# memory-32kx13.net
KiCad netlist of a schematic drawn in EAGLE
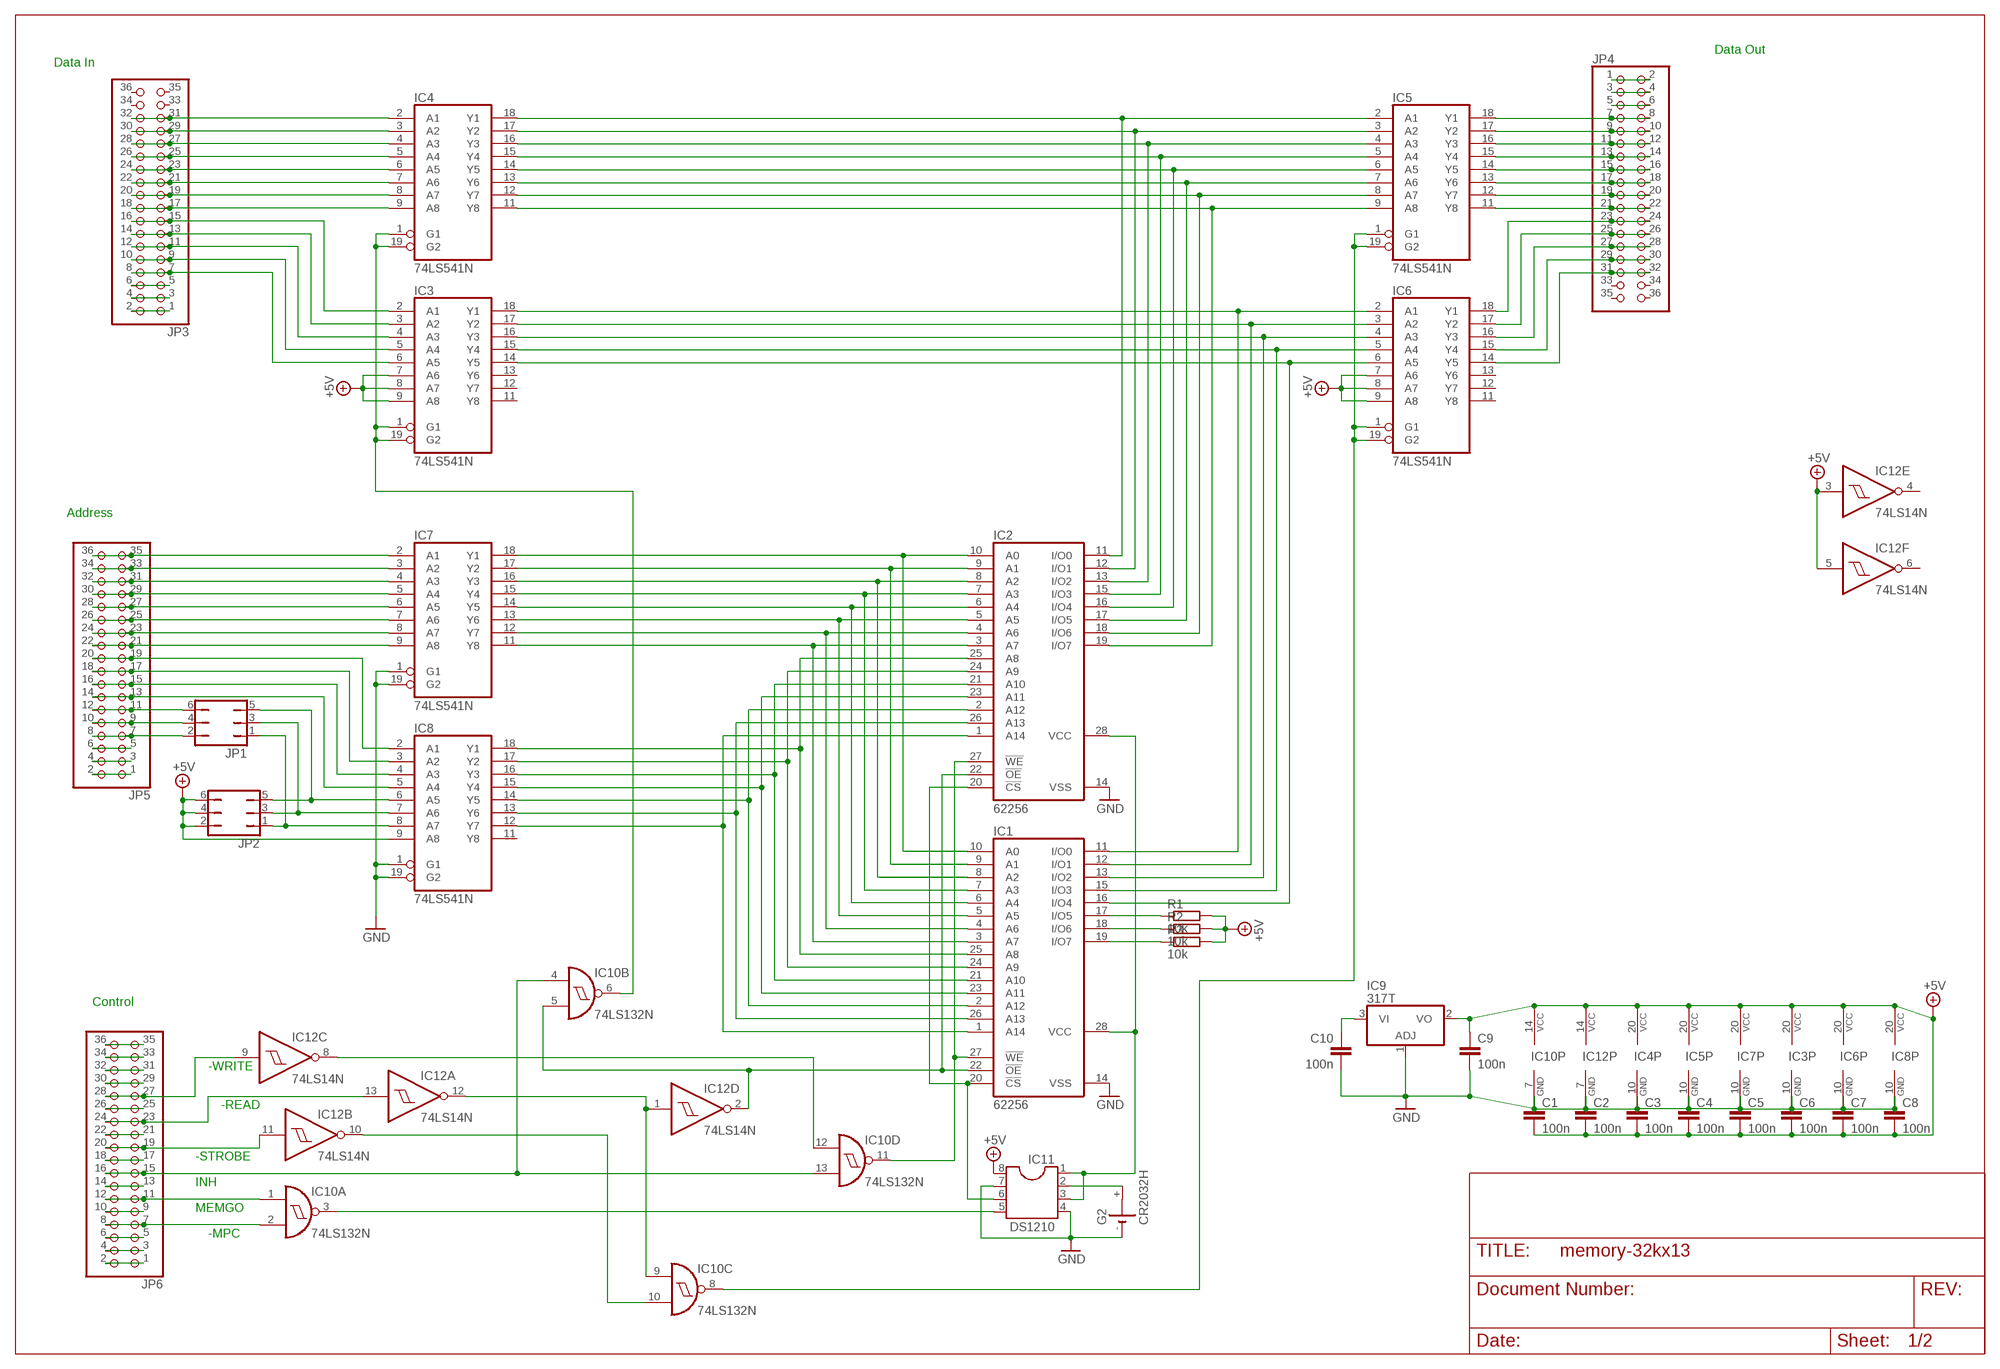
[diagram p0: schematic, sheet 1]
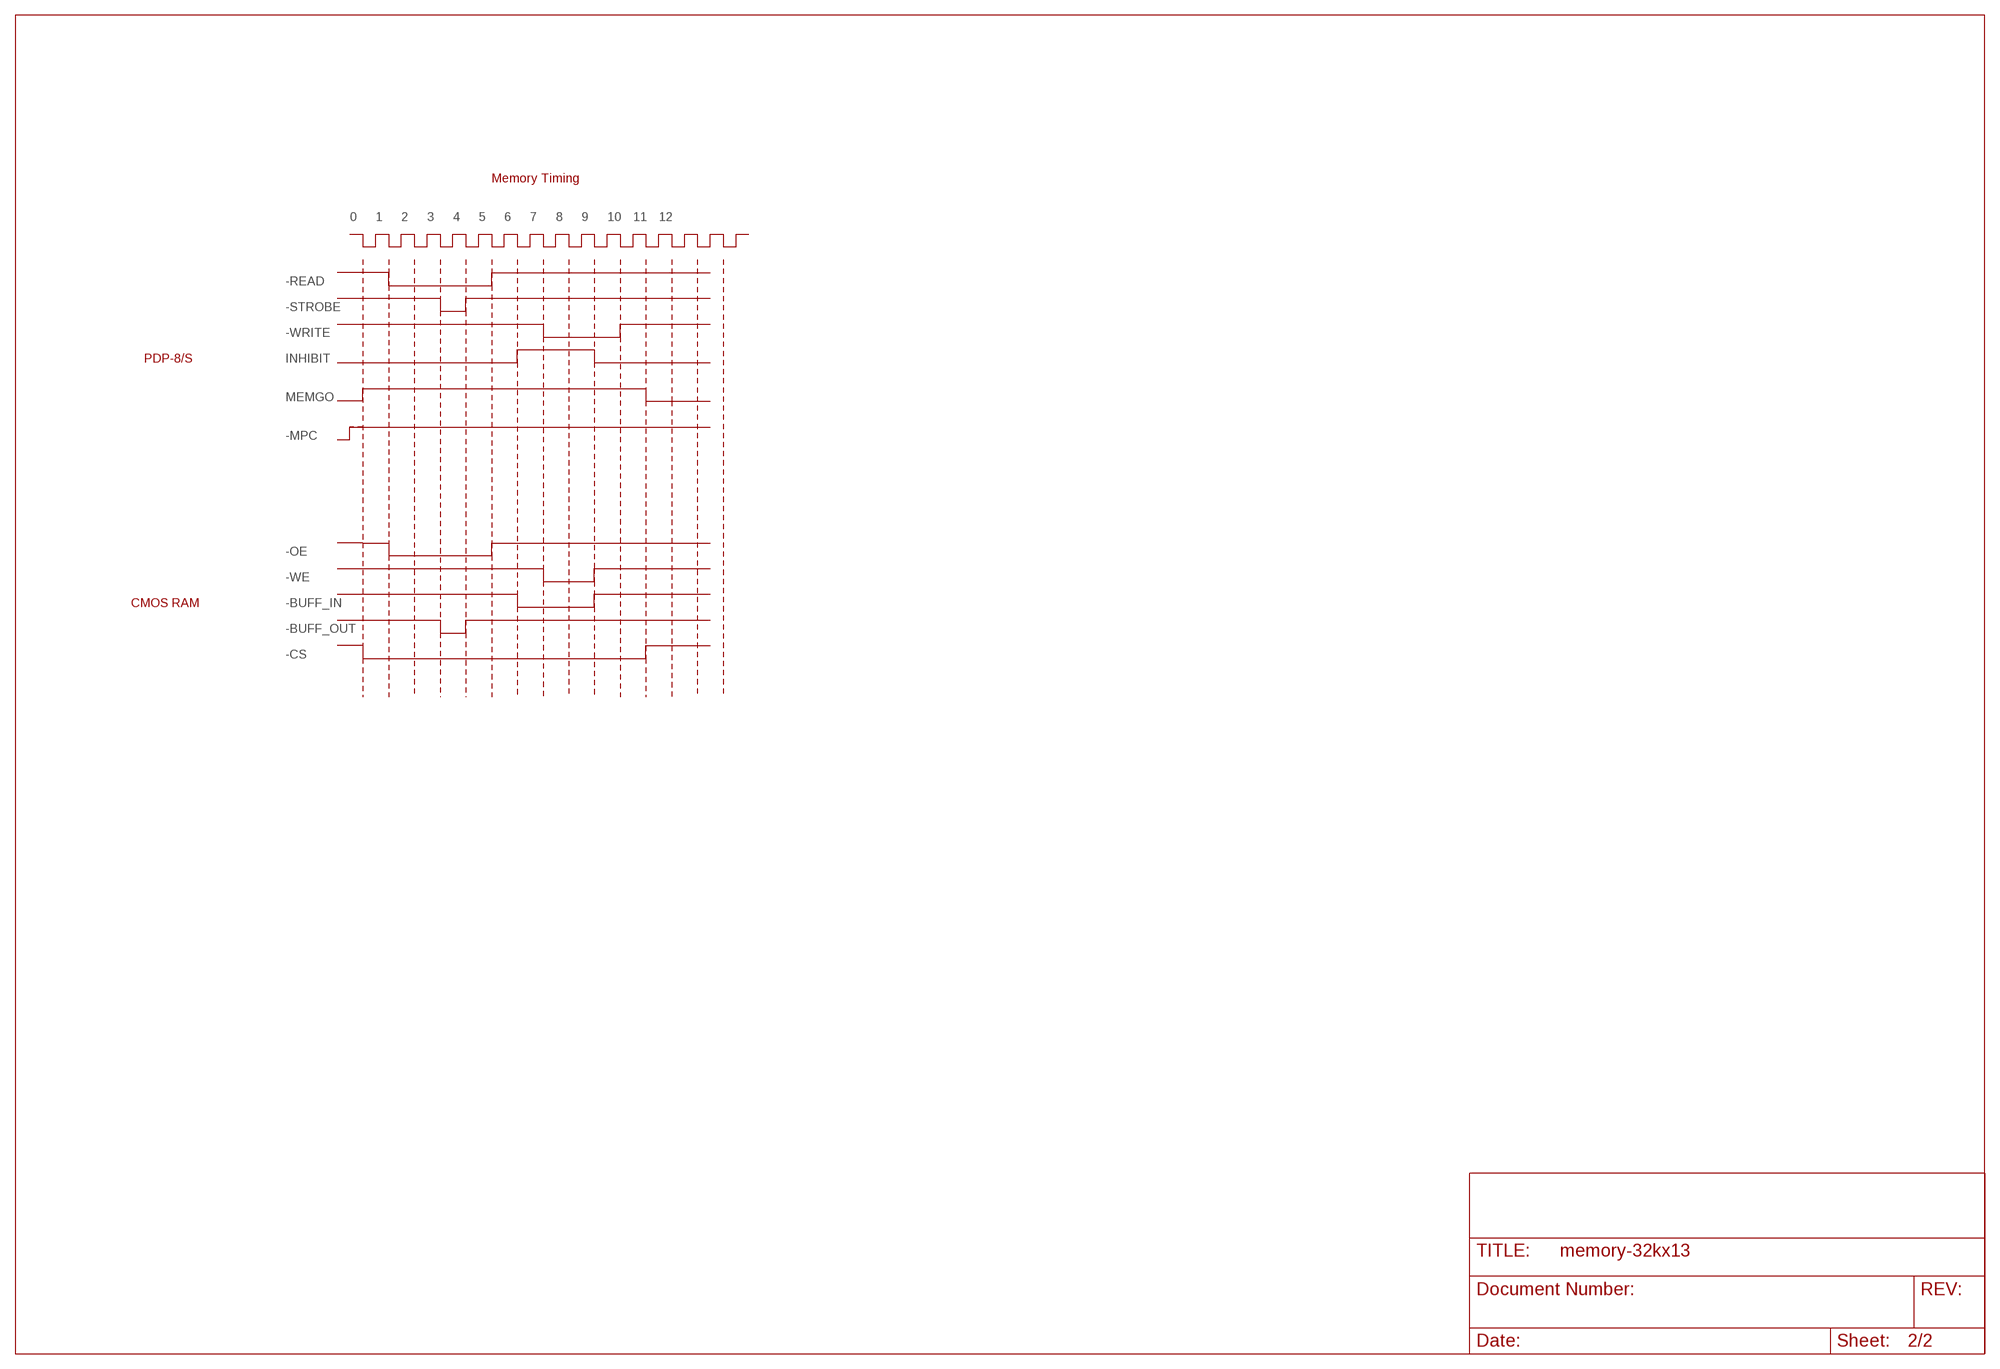
[diagram p1: schematic, sheet 2]

(export (version "E")
  (design (tool "Eeschema 10.0.6"))
  (components
    (comp (ref "C1")
      (value "100n")
      (footprint "eagle-import:C050-024X044")
      (libsource (lib "eagle-import") (part "C-EU050-024X044"))
    )
    (comp (ref "C2")
      (value "100n")
      (footprint "eagle-import:C050-024X044")
      (libsource (lib "eagle-import") (part "C-EU050-024X044"))
    )
    (comp (ref "C3")
      (value "100n")
      (footprint "eagle-import:C050-024X044")
      (libsource (lib "eagle-import") (part "C-EU050-024X044"))
    )
    (comp (ref "C4")
      (value "100n")
      (footprint "eagle-import:C050-024X044")
      (libsource (lib "eagle-import") (part "C-EU050-024X044"))
    )
    (comp (ref "C5")
      (value "100n")
      (footprint "eagle-import:C050-024X044")
      (libsource (lib "eagle-import") (part "C-EU050-024X044"))
    )
    (comp (ref "C6")
      (value "100n")
      (footprint "eagle-import:C050-024X044")
      (libsource (lib "eagle-import") (part "C-EU050-024X044"))
    )
    (comp (ref "C7")
      (value "100n")
      (footprint "eagle-import:C050-024X044")
      (libsource (lib "eagle-import") (part "C-EU050-024X044"))
    )
    (comp (ref "C8")
      (value "100n")
      (footprint "eagle-import:C050-024X044")
      (libsource (lib "eagle-import") (part "C-EU050-024X044"))
    )
    (comp (ref "C9")
      (value "100n")
      (footprint "eagle-import:C050-024X044")
      (libsource (lib "eagle-import") (part "C-EU050-024X044"))
    )
    (comp (ref "C10")
      (value "100n")
      (footprint "eagle-import:C050-024X044")
      (libsource (lib "eagle-import") (part "C-EU050-024X044"))
    )
    (comp (ref "G2")
      (value "CR2032H")
      (footprint "eagle-import:CR2032H")
      (libsource (lib "eagle-import") (part "CR2032H"))
    )
    (comp (ref "IC1")
      (value "62256")
      (footprint "eagle-import:DIL28-6")
      (libsource (lib "eagle-import") (part "62256P"))
    )
    (comp (ref "IC2")
      (value "62256")
      (footprint "eagle-import:DIL28-6")
      (libsource (lib "eagle-import") (part "62256P"))
    )
    (comp (ref "IC3")
      (value "74LS541N")
      (footprint "eagle-import:DIL20")
      (libsource (lib "eagle-import") (part "74541NLS"))
    )
    (comp (ref "IC4")
      (value "74LS541N")
      (footprint "eagle-import:DIL20")
      (libsource (lib "eagle-import") (part "74541NLS"))
    )
    (comp (ref "IC5")
      (value "74LS541N")
      (footprint "eagle-import:DIL20")
      (libsource (lib "eagle-import") (part "74541NLS"))
    )
    (comp (ref "IC6")
      (value "74LS541N")
      (footprint "eagle-import:DIL20")
      (libsource (lib "eagle-import") (part "74541NLS"))
    )
    (comp (ref "IC7")
      (value "74LS541N")
      (footprint "eagle-import:DIL20")
      (libsource (lib "eagle-import") (part "74541NLS"))
    )
    (comp (ref "IC8")
      (value "74LS541N")
      (footprint "eagle-import:DIL20")
      (libsource (lib "eagle-import") (part "74541NLS"))
    )
    (comp (ref "IC9")
      (value "317T")
      (footprint "eagle-import:TO220H")
      (libsource (lib "eagle-import") (part "317T"))
    )
    (comp (ref "IC10")
      (value "74LS132N")
      (footprint "eagle-import:DIL14")
      (libsource (lib "eagle-import") (part "74132NLS"))
    )
    (comp (ref "IC11")
      (value "DS1210")
      (footprint "eagle-import:SOCKET-08")
      (libsource (lib "eagle-import") (part "DIL8S"))
    )
    (comp (ref "IC12")
      (value "74LS14N")
      (footprint "eagle-import:DIL14")
      (libsource (lib "eagle-import") (part "7414NLS"))
    )
    (comp (ref "JP1")
      (value "JP3Q")
      (footprint "eagle-import:JP3Q")
      (libsource (lib "eagle-import") (part "JP3Q"))
    )
    (comp (ref "JP2")
      (value "JP3Q")
      (footprint "eagle-import:JP3Q")
      (libsource (lib "eagle-import") (part "JP3Q"))
    )
    (comp (ref "JP3")
      (value "PINHD-2X18")
      (footprint "eagle-import:2X18")
      (libsource (lib "eagle-import") (part "PINHD-2X18"))
    )
    (comp (ref "JP4")
      (value "PINHD-2X18")
      (footprint "eagle-import:2X18")
      (libsource (lib "eagle-import") (part "PINHD-2X18"))
    )
    (comp (ref "JP5")
      (value "PINHD-2X18")
      (footprint "eagle-import:2X18")
      (libsource (lib "eagle-import") (part "PINHD-2X18"))
    )
    (comp (ref "JP6")
      (value "PINHD-2X18")
      (footprint "eagle-import:2X18")
      (libsource (lib "eagle-import") (part "PINHD-2X18"))
    )
    (comp (ref "R1")
      (value "10k")
      (footprint "eagle-import:0204_7")
      (libsource (lib "eagle-import") (part "R-EU_0204/7"))
    )
    (comp (ref "R2")
      (value "10k")
      (footprint "eagle-import:0204_7")
      (libsource (lib "eagle-import") (part "R-EU_0204/7"))
    )
    (comp (ref "R3")
      (value "10k")
      (footprint "eagle-import:0204_7")
      (libsource (lib "eagle-import") (part "R-EU_0204/7"))
    )
  )
  (nets
    (net (code "1") (name "+5V") (class "Default")
      (node (ref "C1") (pin "2") (pinfunction "2_2") (pintype "passive"))
      (node (ref "C2") (pin "2") (pinfunction "2_2") (pintype "passive"))
      (node (ref "C3") (pin "2") (pinfunction "2_2") (pintype "passive"))
      (node (ref "C4") (pin "2") (pinfunction "2_2") (pintype "passive"))
      (node (ref "C5") (pin "2") (pinfunction "2_2") (pintype "passive"))
      (node (ref "C6") (pin "2") (pinfunction "2_2") (pintype "passive"))
      (node (ref "C7") (pin "2") (pinfunction "2_2") (pintype "passive"))
      (node (ref "C8") (pin "2") (pinfunction "2_2") (pintype "passive"))
      (node (ref "C9") (pin "1") (pinfunction "1_1") (pintype "passive"))
      (node (ref "IC10") (pin "14") (pinfunction "VCC_14") (pintype "power_in"))
      (node (ref "IC11") (pin "8") (pinfunction "8_8") (pintype "passive"))
      (node (ref "IC12") (pin "14") (pinfunction "VCC_14") (pintype "power_in"))
      (node (ref "IC12") (pin "3") (pinfunction "I_3") (pintype "input"))
      (node (ref "IC12") (pin "5") (pinfunction "I_5") (pintype "input"))
      (node (ref "IC3") (pin "20") (pinfunction "VCC_20") (pintype "power_in"))
      (node (ref "IC3") (pin "7") (pinfunction "A6_7") (pintype "input"))
      (node (ref "IC3") (pin "8") (pinfunction "A7_8") (pintype "input"))
      (node (ref "IC3") (pin "9") (pinfunction "A8_9") (pintype "input"))
      (node (ref "IC4") (pin "20") (pinfunction "VCC_20") (pintype "power_in"))
      (node (ref "IC5") (pin "20") (pinfunction "VCC_20") (pintype "power_in"))
      (node (ref "IC6") (pin "20") (pinfunction "VCC_20") (pintype "power_in"))
      (node (ref "IC6") (pin "7") (pinfunction "A6_7") (pintype "input"))
      (node (ref "IC6") (pin "8") (pinfunction "A7_8") (pintype "input"))
      (node (ref "IC6") (pin "9") (pinfunction "A8_9") (pintype "input"))
      (node (ref "IC7") (pin "20") (pinfunction "VCC_20") (pintype "power_in"))
      (node (ref "IC8") (pin "20") (pinfunction "VCC_20") (pintype "power_in"))
      (node (ref "IC8") (pin "9") (pinfunction "A8_9") (pintype "input"))
      (node (ref "IC9") (pin "2") (pinfunction "VO_2") (pintype "passive"))
      (node (ref "JP2") (pin "2") (pinfunction "2_2") (pintype "passive"))
      (node (ref "JP2") (pin "4") (pinfunction "4_4") (pintype "passive"))
      (node (ref "JP2") (pin "6") (pinfunction "6_6") (pintype "passive"))
      (node (ref "R1") (pin "2") (pinfunction "2_2") (pintype "passive"))
      (node (ref "R2") (pin "2") (pinfunction "2_2") (pintype "passive"))
      (node (ref "R3") (pin "2") (pinfunction "2_2") (pintype "passive"))
    )
    (net (code "2") (name "GND") (class "Default")
      (node (ref "C1") (pin "1") (pinfunction "1_1") (pintype "passive"))
      (node (ref "C10") (pin "2") (pinfunction "2_2") (pintype "passive"))
      (node (ref "C2") (pin "1") (pinfunction "1_1") (pintype "passive"))
      (node (ref "C3") (pin "1") (pinfunction "1_1") (pintype "passive"))
      (node (ref "C4") (pin "1") (pinfunction "1_1") (pintype "passive"))
      (node (ref "C5") (pin "1") (pinfunction "1_1") (pintype "passive"))
      (node (ref "C6") (pin "1") (pinfunction "1_1") (pintype "passive"))
      (node (ref "C7") (pin "1") (pinfunction "1_1") (pintype "passive"))
      (node (ref "C8") (pin "1") (pinfunction "1_1") (pintype "passive"))
      (node (ref "C9") (pin "2") (pinfunction "2_2") (pintype "passive"))
      (node (ref "G2") (pin "-") (pinfunction "-_-") (pintype "passive"))
      (node (ref "IC1") (pin "14") (pinfunction "VSS_14") (pintype "power_in"))
      (node (ref "IC10") (pin "7") (pinfunction "GND_7") (pintype "power_in"))
      (node (ref "IC11") (pin "4") (pinfunction "4_4") (pintype "passive"))
      (node (ref "IC11") (pin "7") (pinfunction "7_7") (pintype "passive"))
      (node (ref "IC12") (pin "7") (pinfunction "GND_7") (pintype "power_in"))
      (node (ref "IC2") (pin "14") (pinfunction "VSS_14") (pintype "power_in"))
      (node (ref "IC3") (pin "10") (pinfunction "GND_10") (pintype "power_in"))
      (node (ref "IC4") (pin "10") (pinfunction "GND_10") (pintype "power_in"))
      (node (ref "IC5") (pin "10") (pinfunction "GND_10") (pintype "power_in"))
      (node (ref "IC6") (pin "10") (pinfunction "GND_10") (pintype "power_in"))
      (node (ref "IC7") (pin "1") (pinfunction "G1_1") (pintype "input"))
      (node (ref "IC7") (pin "10") (pinfunction "GND_10") (pintype "power_in"))
      (node (ref "IC7") (pin "19") (pinfunction "G2_19") (pintype "input"))
      (node (ref "IC8") (pin "1") (pinfunction "G1_1") (pintype "input"))
      (node (ref "IC8") (pin "10") (pinfunction "GND_10") (pintype "power_in"))
      (node (ref "IC8") (pin "19") (pinfunction "G2_19") (pintype "input"))
      (node (ref "IC9") (pin "1") (pinfunction "ADJ_1") (pintype "input"))
    )
    (net (code "3") (name "Net-(G2-Pad+)") (class "Default")
      (node (ref "G2") (pin "+") (pinfunction "+_+") (pintype "passive"))
      (node (ref "IC11") (pin "2") (pinfunction "2_2") (pintype "passive"))
    )
    (net (code "4") (name "Net-(IC1-A0)") (class "Default")
      (node (ref "IC1") (pin "10") (pinfunction "A0_10") (pintype "input"))
      (node (ref "IC2") (pin "10") (pinfunction "A0_10") (pintype "input"))
      (node (ref "IC7") (pin "18") (pinfunction "Y1_18") (pintype "tri_state"))
    )
    (net (code "5") (name "Net-(IC1-A1)") (class "Default")
      (node (ref "IC1") (pin "9") (pinfunction "A1_9") (pintype "input"))
      (node (ref "IC2") (pin "9") (pinfunction "A1_9") (pintype "input"))
      (node (ref "IC7") (pin "17") (pinfunction "Y2_17") (pintype "tri_state"))
    )
    (net (code "6") (name "Net-(IC1-A2)") (class "Default")
      (node (ref "IC1") (pin "8") (pinfunction "A2_8") (pintype "input"))
      (node (ref "IC2") (pin "8") (pinfunction "A2_8") (pintype "input"))
      (node (ref "IC7") (pin "16") (pinfunction "Y3_16") (pintype "tri_state"))
    )
    (net (code "7") (name "Net-(IC1-A3)") (class "Default")
      (node (ref "IC1") (pin "7") (pinfunction "A3_7") (pintype "input"))
      (node (ref "IC2") (pin "7") (pinfunction "A3_7") (pintype "input"))
      (node (ref "IC7") (pin "15") (pinfunction "Y4_15") (pintype "tri_state"))
    )
    (net (code "8") (name "Net-(IC1-A4)") (class "Default")
      (node (ref "IC1") (pin "6") (pinfunction "A4_6") (pintype "input"))
      (node (ref "IC2") (pin "6") (pinfunction "A4_6") (pintype "input"))
      (node (ref "IC7") (pin "14") (pinfunction "Y5_14") (pintype "tri_state"))
    )
    (net (code "9") (name "Net-(IC1-A5)") (class "Default")
      (node (ref "IC1") (pin "5") (pinfunction "A5_5") (pintype "input"))
      (node (ref "IC2") (pin "5") (pinfunction "A5_5") (pintype "input"))
      (node (ref "IC7") (pin "13") (pinfunction "Y6_13") (pintype "tri_state"))
    )
    (net (code "10") (name "Net-(IC1-A6)") (class "Default")
      (node (ref "IC1") (pin "4") (pinfunction "A6_4") (pintype "input"))
      (node (ref "IC2") (pin "4") (pinfunction "A6_4") (pintype "input"))
      (node (ref "IC7") (pin "12") (pinfunction "Y7_12") (pintype "tri_state"))
    )
    (net (code "11") (name "Net-(IC1-A7)") (class "Default")
      (node (ref "IC1") (pin "3") (pinfunction "A7_3") (pintype "input"))
      (node (ref "IC2") (pin "3") (pinfunction "A7_3") (pintype "input"))
      (node (ref "IC7") (pin "11") (pinfunction "Y8_11") (pintype "tri_state"))
    )
    (net (code "12") (name "Net-(IC1-A8)") (class "Default")
      (node (ref "IC1") (pin "25") (pinfunction "A8_25") (pintype "input"))
      (node (ref "IC2") (pin "25") (pinfunction "A8_25") (pintype "input"))
      (node (ref "IC8") (pin "18") (pinfunction "Y1_18") (pintype "tri_state"))
    )
    (net (code "13") (name "Net-(IC1-A9)") (class "Default")
      (node (ref "IC1") (pin "24") (pinfunction "A9_24") (pintype "input"))
      (node (ref "IC2") (pin "24") (pinfunction "A9_24") (pintype "input"))
      (node (ref "IC8") (pin "17") (pinfunction "Y2_17") (pintype "tri_state"))
    )
    (net (code "14") (name "Net-(IC1-A10)") (class "Default")
      (node (ref "IC1") (pin "21") (pinfunction "A10_21") (pintype "input"))
      (node (ref "IC2") (pin "21") (pinfunction "A10_21") (pintype "input"))
      (node (ref "IC8") (pin "16") (pinfunction "Y3_16") (pintype "tri_state"))
    )
    (net (code "15") (name "Net-(IC1-A11)") (class "Default")
      (node (ref "IC1") (pin "23") (pinfunction "A11_23") (pintype "input"))
      (node (ref "IC2") (pin "23") (pinfunction "A11_23") (pintype "input"))
      (node (ref "IC8") (pin "15") (pinfunction "Y4_15") (pintype "tri_state"))
    )
    (net (code "16") (name "Net-(IC1-A12)") (class "Default")
      (node (ref "IC1") (pin "2") (pinfunction "A12_2") (pintype "input"))
      (node (ref "IC2") (pin "2") (pinfunction "A12_2") (pintype "input"))
      (node (ref "IC8") (pin "14") (pinfunction "Y5_14") (pintype "tri_state"))
    )
    (net (code "17") (name "Net-(IC1-A13)") (class "Default")
      (node (ref "IC1") (pin "26") (pinfunction "A13_26") (pintype "input"))
      (node (ref "IC2") (pin "26") (pinfunction "A13_26") (pintype "input"))
      (node (ref "IC8") (pin "13") (pinfunction "Y6_13") (pintype "tri_state"))
    )
    (net (code "18") (name "Net-(IC1-A14)") (class "Default")
      (node (ref "IC1") (pin "1") (pinfunction "A14_1") (pintype "input"))
      (node (ref "IC2") (pin "1") (pinfunction "A14_1") (pintype "input"))
      (node (ref "IC8") (pin "12") (pinfunction "Y7_12") (pintype "tri_state"))
    )
    (net (code "19") (name "Net-(IC1-I{slash}O0)") (class "Default")
      (node (ref "IC1") (pin "11") (pinfunction "I/O0_11") (pintype "bidirectional"))
      (node (ref "IC3") (pin "18") (pinfunction "Y1_18") (pintype "tri_state"))
      (node (ref "IC6") (pin "2") (pinfunction "A1_2") (pintype "input"))
    )
    (net (code "20") (name "Net-(IC1-I{slash}O1)") (class "Default")
      (node (ref "IC1") (pin "12") (pinfunction "I/O1_12") (pintype "bidirectional"))
      (node (ref "IC3") (pin "17") (pinfunction "Y2_17") (pintype "tri_state"))
      (node (ref "IC6") (pin "3") (pinfunction "A2_3") (pintype "input"))
    )
    (net (code "21") (name "Net-(IC1-I{slash}O2)") (class "Default")
      (node (ref "IC1") (pin "13") (pinfunction "I/O2_13") (pintype "bidirectional"))
      (node (ref "IC3") (pin "16") (pinfunction "Y3_16") (pintype "tri_state"))
      (node (ref "IC6") (pin "4") (pinfunction "A3_4") (pintype "input"))
    )
    (net (code "22") (name "Net-(IC1-I{slash}O3)") (class "Default")
      (node (ref "IC1") (pin "15") (pinfunction "I/O3_15") (pintype "bidirectional"))
      (node (ref "IC3") (pin "15") (pinfunction "Y4_15") (pintype "tri_state"))
      (node (ref "IC6") (pin "5") (pinfunction "A4_5") (pintype "input"))
    )
    (net (code "23") (name "Net-(IC1-I{slash}O4)") (class "Default")
      (node (ref "IC1") (pin "16") (pinfunction "I/O4_16") (pintype "bidirectional"))
      (node (ref "IC3") (pin "14") (pinfunction "Y5_14") (pintype "tri_state"))
      (node (ref "IC6") (pin "6") (pinfunction "A5_6") (pintype "input"))
    )
    (net (code "24") (name "Net-(IC1-I{slash}O5)") (class "Default")
      (node (ref "IC1") (pin "17") (pinfunction "I/O5_17") (pintype "bidirectional"))
      (node (ref "R1") (pin "1") (pinfunction "1_1") (pintype "passive"))
    )
    (net (code "25") (name "Net-(IC1-I{slash}O6)") (class "Default")
      (node (ref "IC1") (pin "18") (pinfunction "I/O6_18") (pintype "bidirectional"))
      (node (ref "R2") (pin "1") (pinfunction "1_1") (pintype "passive"))
    )
    (net (code "26") (name "Net-(IC1-I{slash}O7)") (class "Default")
      (node (ref "IC1") (pin "19") (pinfunction "I/O7_19") (pintype "bidirectional"))
      (node (ref "R3") (pin "1") (pinfunction "1_1") (pintype "passive"))
    )
    (net (code "27") (name "Net-(IC1-VCC)") (class "Default")
      (node (ref "IC1") (pin "28") (pinfunction "VCC_28") (pintype "power_in"))
      (node (ref "IC11") (pin "1") (pinfunction "1_1") (pintype "passive"))
      (node (ref "IC11") (pin "3") (pinfunction "3_3") (pintype "passive"))
      (node (ref "IC2") (pin "28") (pinfunction "VCC_28") (pintype "power_in"))
    )
    (net (code "28") (name "Net-(IC1-~{CS})") (class "Default")
      (node (ref "IC1") (pin "20") (pinfunction "~{CS}_20") (pintype "input"))
      (node (ref "IC11") (pin "6") (pinfunction "6_6") (pintype "passive"))
      (node (ref "IC2") (pin "20") (pinfunction "~{CS}_20") (pintype "input"))
    )
    (net (code "29") (name "Net-(IC1-~{OE})") (class "Default")
      (node (ref "IC1") (pin "22") (pinfunction "~{OE}_22") (pintype "input"))
      (node (ref "IC10") (pin "5") (pinfunction "I1_5") (pintype "input"))
      (node (ref "IC12") (pin "2") (pinfunction "O_2") (pintype "output"))
      (node (ref "IC2") (pin "22") (pinfunction "~{OE}_22") (pintype "input"))
    )
    (net (code "30") (name "Net-(IC1-~{WE})") (class "Default")
      (node (ref "IC1") (pin "27") (pinfunction "~{WE}_27") (pintype "input"))
      (node (ref "IC10") (pin "11") (pinfunction "O_11") (pintype "output"))
      (node (ref "IC2") (pin "27") (pinfunction "~{WE}_27") (pintype "input"))
    )
    (net (code "31") (name "Net-(IC2-I{slash}O0)") (class "Default")
      (node (ref "IC2") (pin "11") (pinfunction "I/O0_11") (pintype "bidirectional"))
      (node (ref "IC4") (pin "18") (pinfunction "Y1_18") (pintype "tri_state"))
      (node (ref "IC5") (pin "2") (pinfunction "A1_2") (pintype "input"))
    )
    (net (code "32") (name "Net-(IC2-I{slash}O1)") (class "Default")
      (node (ref "IC2") (pin "12") (pinfunction "I/O1_12") (pintype "bidirectional"))
      (node (ref "IC4") (pin "17") (pinfunction "Y2_17") (pintype "tri_state"))
      (node (ref "IC5") (pin "3") (pinfunction "A2_3") (pintype "input"))
    )
    (net (code "33") (name "Net-(IC2-I{slash}O2)") (class "Default")
      (node (ref "IC2") (pin "13") (pinfunction "I/O2_13") (pintype "bidirectional"))
      (node (ref "IC4") (pin "16") (pinfunction "Y3_16") (pintype "tri_state"))
      (node (ref "IC5") (pin "4") (pinfunction "A3_4") (pintype "input"))
    )
    (net (code "34") (name "Net-(IC2-I{slash}O3)") (class "Default")
      (node (ref "IC2") (pin "15") (pinfunction "I/O3_15") (pintype "bidirectional"))
      (node (ref "IC4") (pin "15") (pinfunction "Y4_15") (pintype "tri_state"))
      (node (ref "IC5") (pin "5") (pinfunction "A4_5") (pintype "input"))
    )
    (net (code "35") (name "Net-(IC2-I{slash}O4)") (class "Default")
      (node (ref "IC2") (pin "16") (pinfunction "I/O4_16") (pintype "bidirectional"))
      (node (ref "IC4") (pin "14") (pinfunction "Y5_14") (pintype "tri_state"))
      (node (ref "IC5") (pin "6") (pinfunction "A5_6") (pintype "input"))
    )
    (net (code "36") (name "Net-(IC2-I{slash}O5)") (class "Default")
      (node (ref "IC2") (pin "17") (pinfunction "I/O5_17") (pintype "bidirectional"))
      (node (ref "IC4") (pin "13") (pinfunction "Y6_13") (pintype "tri_state"))
      (node (ref "IC5") (pin "7") (pinfunction "A6_7") (pintype "input"))
    )
    (net (code "37") (name "Net-(IC2-I{slash}O6)") (class "Default")
      (node (ref "IC2") (pin "18") (pinfunction "I/O6_18") (pintype "bidirectional"))
      (node (ref "IC4") (pin "12") (pinfunction "Y7_12") (pintype "tri_state"))
      (node (ref "IC5") (pin "8") (pinfunction "A7_8") (pintype "input"))
    )
    (net (code "38") (name "Net-(IC2-I{slash}O7)") (class "Default")
      (node (ref "IC2") (pin "19") (pinfunction "I/O7_19") (pintype "bidirectional"))
      (node (ref "IC4") (pin "11") (pinfunction "Y8_11") (pintype "tri_state"))
      (node (ref "IC5") (pin "9") (pinfunction "A8_9") (pintype "input"))
    )
    (net (code "39") (name "Net-(IC3A-A1)") (class "Default")
      (node (ref "IC3") (pin "2") (pinfunction "A1_2") (pintype "input"))
      (node (ref "JP3") (pin "15") (pinfunction "15_15") (pintype "passive"))
      (node (ref "JP3") (pin "16") (pinfunction "16_16") (pintype "passive"))
    )
    (net (code "40") (name "Net-(IC3A-A2)") (class "Default")
      (node (ref "IC3") (pin "3") (pinfunction "A2_3") (pintype "input"))
      (node (ref "JP3") (pin "13") (pinfunction "13_13") (pintype "passive"))
      (node (ref "JP3") (pin "14") (pinfunction "14_14") (pintype "passive"))
    )
    (net (code "41") (name "Net-(IC3A-A3)") (class "Default")
      (node (ref "IC3") (pin "4") (pinfunction "A3_4") (pintype "input"))
      (node (ref "JP3") (pin "11") (pinfunction "11_11") (pintype "passive"))
      (node (ref "JP3") (pin "12") (pinfunction "12_12") (pintype "passive"))
    )
    (net (code "42") (name "Net-(IC3A-A4)") (class "Default")
      (node (ref "IC3") (pin "5") (pinfunction "A4_5") (pintype "input"))
      (node (ref "JP3") (pin "10") (pinfunction "10_10") (pintype "passive"))
      (node (ref "JP3") (pin "9") (pinfunction "9_9") (pintype "passive"))
    )
    (net (code "43") (name "Net-(IC3A-A5)") (class "Default")
      (node (ref "IC3") (pin "6") (pinfunction "A5_6") (pintype "input"))
      (node (ref "JP3") (pin "7") (pinfunction "7_7") (pintype "passive"))
      (node (ref "JP3") (pin "8") (pinfunction "8_8") (pintype "passive"))
    )
    (net (code "44") (name "Net-(IC4A-A1)") (class "Default")
      (node (ref "IC4") (pin "2") (pinfunction "A1_2") (pintype "input"))
      (node (ref "JP3") (pin "31") (pinfunction "31_31") (pintype "passive"))
      (node (ref "JP3") (pin "32") (pinfunction "32_32") (pintype "passive"))
    )
    (net (code "45") (name "Net-(IC4A-A2)") (class "Default")
      (node (ref "IC4") (pin "3") (pinfunction "A2_3") (pintype "input"))
      (node (ref "JP3") (pin "29") (pinfunction "29_29") (pintype "passive"))
      (node (ref "JP3") (pin "30") (pinfunction "30_30") (pintype "passive"))
    )
    (net (code "46") (name "Net-(IC4A-A3)") (class "Default")
      (node (ref "IC4") (pin "4") (pinfunction "A3_4") (pintype "input"))
      (node (ref "JP3") (pin "27") (pinfunction "27_27") (pintype "passive"))
      (node (ref "JP3") (pin "28") (pinfunction "28_28") (pintype "passive"))
    )
    (net (code "47") (name "Net-(IC4A-A4)") (class "Default")
      (node (ref "IC4") (pin "5") (pinfunction "A4_5") (pintype "input"))
      (node (ref "JP3") (pin "25") (pinfunction "25_25") (pintype "passive"))
      (node (ref "JP3") (pin "26") (pinfunction "26_26") (pintype "passive"))
    )
    (net (code "48") (name "Net-(IC4A-A5)") (class "Default")
      (node (ref "IC4") (pin "6") (pinfunction "A5_6") (pintype "input"))
      (node (ref "JP3") (pin "23") (pinfunction "23_23") (pintype "passive"))
      (node (ref "JP3") (pin "24") (pinfunction "24_24") (pintype "passive"))
    )
    (net (code "49") (name "Net-(IC4A-A6)") (class "Default")
      (node (ref "IC4") (pin "7") (pinfunction "A6_7") (pintype "input"))
      (node (ref "JP3") (pin "21") (pinfunction "21_21") (pintype "passive"))
      (node (ref "JP3") (pin "22") (pinfunction "22_22") (pintype "passive"))
    )
    (net (code "50") (name "Net-(IC4A-A7)") (class "Default")
      (node (ref "IC4") (pin "8") (pinfunction "A7_8") (pintype "input"))
      (node (ref "JP3") (pin "19") (pinfunction "19_19") (pintype "passive"))
      (node (ref "JP3") (pin "20") (pinfunction "20_20") (pintype "passive"))
    )
    (net (code "51") (name "Net-(IC4A-A8)") (class "Default")
      (node (ref "IC4") (pin "9") (pinfunction "A8_9") (pintype "input"))
      (node (ref "JP3") (pin "17") (pinfunction "17_17") (pintype "passive"))
      (node (ref "JP3") (pin "18") (pinfunction "18_18") (pintype "passive"))
    )
    (net (code "52") (name "Net-(IC5A-Y1)") (class "Default")
      (node (ref "IC5") (pin "18") (pinfunction "Y1_18") (pintype "tri_state"))
      (node (ref "JP4") (pin "7") (pinfunction "7_7") (pintype "passive"))
      (node (ref "JP4") (pin "8") (pinfunction "8_8") (pintype "passive"))
    )
    (net (code "53") (name "Net-(IC5A-Y2)") (class "Default")
      (node (ref "IC5") (pin "17") (pinfunction "Y2_17") (pintype "tri_state"))
      (node (ref "JP4") (pin "10") (pinfunction "10_10") (pintype "passive"))
      (node (ref "JP4") (pin "9") (pinfunction "9_9") (pintype "passive"))
    )
    (net (code "54") (name "Net-(IC5A-Y3)") (class "Default")
      (node (ref "IC5") (pin "16") (pinfunction "Y3_16") (pintype "tri_state"))
      (node (ref "JP4") (pin "11") (pinfunction "11_11") (pintype "passive"))
      (node (ref "JP4") (pin "12") (pinfunction "12_12") (pintype "passive"))
    )
    (net (code "55") (name "Net-(IC5A-Y4)") (class "Default")
      (node (ref "IC5") (pin "15") (pinfunction "Y4_15") (pintype "tri_state"))
      (node (ref "JP4") (pin "13") (pinfunction "13_13") (pintype "passive"))
      (node (ref "JP4") (pin "14") (pinfunction "14_14") (pintype "passive"))
    )
    (net (code "56") (name "Net-(IC5A-Y5)") (class "Default")
      (node (ref "IC5") (pin "14") (pinfunction "Y5_14") (pintype "tri_state"))
      (node (ref "JP4") (pin "15") (pinfunction "15_15") (pintype "passive"))
      (node (ref "JP4") (pin "16") (pinfunction "16_16") (pintype "passive"))
    )
    (net (code "57") (name "Net-(IC5A-Y6)") (class "Default")
      (node (ref "IC5") (pin "13") (pinfunction "Y6_13") (pintype "tri_state"))
      (node (ref "JP4") (pin "17") (pinfunction "17_17") (pintype "passive"))
      (node (ref "JP4") (pin "18") (pinfunction "18_18") (pintype "passive"))
    )
    (net (code "58") (name "Net-(IC5A-Y7)") (class "Default")
      (node (ref "IC5") (pin "12") (pinfunction "Y7_12") (pintype "tri_state"))
      (node (ref "JP4") (pin "19") (pinfunction "19_19") (pintype "passive"))
      (node (ref "JP4") (pin "20") (pinfunction "20_20") (pintype "passive"))
    )
    (net (code "59") (name "Net-(IC5A-Y8)") (class "Default")
      (node (ref "IC5") (pin "11") (pinfunction "Y8_11") (pintype "tri_state"))
      (node (ref "JP4") (pin "21") (pinfunction "21_21") (pintype "passive"))
      (node (ref "JP4") (pin "22") (pinfunction "22_22") (pintype "passive"))
    )
    (net (code "60") (name "Net-(IC6A-Y1)") (class "Default")
      (node (ref "IC6") (pin "18") (pinfunction "Y1_18") (pintype "tri_state"))
      (node (ref "JP4") (pin "23") (pinfunction "23_23") (pintype "passive"))
      (node (ref "JP4") (pin "24") (pinfunction "24_24") (pintype "passive"))
    )
    (net (code "61") (name "Net-(IC6A-Y2)") (class "Default")
      (node (ref "IC6") (pin "17") (pinfunction "Y2_17") (pintype "tri_state"))
      (node (ref "JP4") (pin "25") (pinfunction "25_25") (pintype "passive"))
      (node (ref "JP4") (pin "26") (pinfunction "26_26") (pintype "passive"))
    )
    (net (code "62") (name "Net-(IC6A-Y3)") (class "Default")
      (node (ref "IC6") (pin "16") (pinfunction "Y3_16") (pintype "tri_state"))
      (node (ref "JP4") (pin "27") (pinfunction "27_27") (pintype "passive"))
      (node (ref "JP4") (pin "28") (pinfunction "28_28") (pintype "passive"))
    )
    (net (code "63") (name "Net-(IC6A-Y4)") (class "Default")
      (node (ref "IC6") (pin "15") (pinfunction "Y4_15") (pintype "tri_state"))
      (node (ref "JP4") (pin "29") (pinfunction "29_29") (pintype "passive"))
      (node (ref "JP4") (pin "30") (pinfunction "30_30") (pintype "passive"))
    )
    (net (code "64") (name "Net-(IC6A-Y5)") (class "Default")
      (node (ref "IC6") (pin "14") (pinfunction "Y5_14") (pintype "tri_state"))
      (node (ref "JP4") (pin "31") (pinfunction "31_31") (pintype "passive"))
      (node (ref "JP4") (pin "32") (pinfunction "32_32") (pintype "passive"))
    )
    (net (code "65") (name "Net-(IC7A-A1)") (class "Default")
      (node (ref "IC7") (pin "2") (pinfunction "A1_2") (pintype "input"))
      (node (ref "JP5") (pin "35") (pinfunction "35_35") (pintype "passive"))
      (node (ref "JP5") (pin "36") (pinfunction "36_36") (pintype "passive"))
    )
    (net (code "66") (name "Net-(IC7A-A2)") (class "Default")
      (node (ref "IC7") (pin "3") (pinfunction "A2_3") (pintype "input"))
      (node (ref "JP5") (pin "33") (pinfunction "33_33") (pintype "passive"))
      (node (ref "JP5") (pin "34") (pinfunction "34_34") (pintype "passive"))
    )
    (net (code "67") (name "Net-(IC7A-A3)") (class "Default")
      (node (ref "IC7") (pin "4") (pinfunction "A3_4") (pintype "input"))
      (node (ref "JP5") (pin "31") (pinfunction "31_31") (pintype "passive"))
      (node (ref "JP5") (pin "32") (pinfunction "32_32") (pintype "passive"))
    )
    (net (code "68") (name "Net-(IC7A-A4)") (class "Default")
      (node (ref "IC7") (pin "5") (pinfunction "A4_5") (pintype "input"))
      (node (ref "JP5") (pin "29") (pinfunction "29_29") (pintype "passive"))
      (node (ref "JP5") (pin "30") (pinfunction "30_30") (pintype "passive"))
    )
    (net (code "69") (name "Net-(IC7A-A5)") (class "Default")
      (node (ref "IC7") (pin "6") (pinfunction "A5_6") (pintype "input"))
      (node (ref "JP5") (pin "27") (pinfunction "27_27") (pintype "passive"))
      (node (ref "JP5") (pin "28") (pinfunction "28_28") (pintype "passive"))
    )
    (net (code "70") (name "Net-(IC7A-A6)") (class "Default")
      (node (ref "IC7") (pin "7") (pinfunction "A6_7") (pintype "input"))
      (node (ref "JP5") (pin "25") (pinfunction "25_25") (pintype "passive"))
      (node (ref "JP5") (pin "26") (pinfunction "26_26") (pintype "passive"))
    )
    (net (code "71") (name "Net-(IC7A-A7)") (class "Default")
      (node (ref "IC7") (pin "8") (pinfunction "A7_8") (pintype "input"))
      (node (ref "JP5") (pin "23") (pinfunction "23_23") (pintype "passive"))
      (node (ref "JP5") (pin "24") (pinfunction "24_24") (pintype "passive"))
    )
    (net (code "72") (name "Net-(IC7A-A8)") (class "Default")
      (node (ref "IC7") (pin "9") (pinfunction "A8_9") (pintype "input"))
      (node (ref "JP5") (pin "21") (pinfunction "21_21") (pintype "passive"))
      (node (ref "JP5") (pin "22") (pinfunction "22_22") (pintype "passive"))
    )
    (net (code "73") (name "Net-(IC8A-A1)") (class "Default")
      (node (ref "IC8") (pin "2") (pinfunction "A1_2") (pintype "input"))
      (node (ref "JP5") (pin "19") (pinfunction "19_19") (pintype "passive"))
      (node (ref "JP5") (pin "20") (pinfunction "20_20") (pintype "passive"))
    )
    (net (code "74") (name "Net-(IC8A-A2)") (class "Default")
      (node (ref "IC8") (pin "3") (pinfunction "A2_3") (pintype "input"))
      (node (ref "JP5") (pin "17") (pinfunction "17_17") (pintype "passive"))
      (node (ref "JP5") (pin "18") (pinfunction "18_18") (pintype "passive"))
    )
    (net (code "75") (name "Net-(IC8A-A3)") (class "Default")
      (node (ref "IC8") (pin "4") (pinfunction "A3_4") (pintype "input"))
      (node (ref "JP5") (pin "15") (pinfunction "15_15") (pintype "passive"))
      (node (ref "JP5") (pin "16") (pinfunction "16_16") (pintype "passive"))
    )
    (net (code "76") (name "Net-(IC8A-A4)") (class "Default")
      (node (ref "IC8") (pin "5") (pinfunction "A4_5") (pintype "input"))
      (node (ref "JP5") (pin "13") (pinfunction "13_13") (pintype "passive"))
      (node (ref "JP5") (pin "14") (pinfunction "14_14") (pintype "passive"))
    )
    (net (code "77") (name "Net-(IC8A-A5)") (class "Default")
      (node (ref "IC8") (pin "6") (pinfunction "A5_6") (pintype "input"))
      (node (ref "JP1") (pin "5") (pinfunction "5_5") (pintype "passive"))
      (node (ref "JP2") (pin "5") (pinfunction "5_5") (pintype "passive"))
    )
    (net (code "78") (name "Net-(IC8A-A6)") (class "Default")
      (node (ref "IC8") (pin "7") (pinfunction "A6_7") (pintype "input"))
      (node (ref "JP1") (pin "3") (pinfunction "3_3") (pintype "passive"))
      (node (ref "JP2") (pin "3") (pinfunction "3_3") (pintype "passive"))
    )
    (net (code "79") (name "Net-(IC8A-A7)") (class "Default")
      (node (ref "IC8") (pin "8") (pinfunction "A7_8") (pintype "input"))
      (node (ref "JP1") (pin "1") (pinfunction "1_1") (pintype "passive"))
      (node (ref "JP2") (pin "1") (pinfunction "1_1") (pintype "passive"))
    )
    (net (code "80") (name "Net-(IC9-VI)") (class "Default")
      (node (ref "C10") (pin "1") (pinfunction "1_1") (pintype "passive"))
      (node (ref "IC9") (pin "3") (pinfunction "VI_3") (pintype "input"))
    )
    (net (code "81") (name "Net-(IC10A-I0)") (class "Default")
      (node (ref "IC10") (pin "1") (pinfunction "I0_1") (pintype "input"))
      (node (ref "JP6") (pin "11") (pinfunction "11_11") (pintype "passive"))
      (node (ref "JP6") (pin "12") (pinfunction "12_12") (pintype "passive"))
    )
    (net (code "82") (name "Net-(IC10A-I1)") (class "Default")
      (node (ref "IC10") (pin "2") (pinfunction "I1_2") (pintype "input"))
      (node (ref "JP6") (pin "7") (pinfunction "7_7") (pintype "passive"))
      (node (ref "JP6") (pin "8") (pinfunction "8_8") (pintype "passive"))
    )
    (net (code "83") (name "Net-(IC10A-O)") (class "Default")
      (node (ref "IC10") (pin "3") (pinfunction "O_3") (pintype "output"))
      (node (ref "IC11") (pin "5") (pinfunction "5_5") (pintype "passive"))
    )
    (net (code "84") (name "Net-(IC10B-I0)") (class "Default")
      (node (ref "IC10") (pin "13") (pinfunction "I1_13") (pintype "input"))
      (node (ref "IC10") (pin "4") (pinfunction "I0_4") (pintype "input"))
      (node (ref "JP6") (pin "15") (pinfunction "15_15") (pintype "passive"))
      (node (ref "JP6") (pin "16") (pinfunction "16_16") (pintype "passive"))
    )
    (net (code "85") (name "Net-(IC10B-O)") (class "Default")
      (node (ref "IC10") (pin "6") (pinfunction "O_6") (pintype "output"))
      (node (ref "IC3") (pin "1") (pinfunction "G1_1") (pintype "input"))
      (node (ref "IC3") (pin "19") (pinfunction "G2_19") (pintype "input"))
      (node (ref "IC4") (pin "1") (pinfunction "G1_1") (pintype "input"))
      (node (ref "IC4") (pin "19") (pinfunction "G2_19") (pintype "input"))
    )
    (net (code "86") (name "Net-(IC10C-I0)") (class "Default")
      (node (ref "IC10") (pin "9") (pinfunction "I0_9") (pintype "input"))
      (node (ref "IC12") (pin "1") (pinfunction "I_1") (pintype "input"))
      (node (ref "IC12") (pin "12") (pinfunction "O_12") (pintype "output"))
    )
    (net (code "87") (name "Net-(IC10C-I1)") (class "Default")
      (node (ref "IC10") (pin "10") (pinfunction "I1_10") (pintype "input"))
      (node (ref "IC12") (pin "10") (pinfunction "O_10") (pintype "output"))
    )
    (net (code "88") (name "Net-(IC10C-O)") (class "Default")
      (node (ref "IC10") (pin "8") (pinfunction "O_8") (pintype "output"))
      (node (ref "IC5") (pin "1") (pinfunction "G1_1") (pintype "input"))
      (node (ref "IC5") (pin "19") (pinfunction "G2_19") (pintype "input"))
      (node (ref "IC6") (pin "1") (pinfunction "G1_1") (pintype "input"))
      (node (ref "IC6") (pin "19") (pinfunction "G2_19") (pintype "input"))
    )
    (net (code "89") (name "Net-(IC10D-I0)") (class "Default")
      (node (ref "IC10") (pin "12") (pinfunction "I0_12") (pintype "input"))
      (node (ref "IC12") (pin "8") (pinfunction "O_8") (pintype "output"))
    )
    (net (code "90") (name "Net-(IC12A-I)") (class "Default")
      (node (ref "IC12") (pin "13") (pinfunction "I_13") (pintype "input"))
      (node (ref "JP6") (pin "23") (pinfunction "23_23") (pintype "passive"))
      (node (ref "JP6") (pin "24") (pinfunction "24_24") (pintype "passive"))
    )
    (net (code "91") (name "Net-(IC12B-I)") (class "Default")
      (node (ref "IC12") (pin "11") (pinfunction "I_11") (pintype "input"))
      (node (ref "JP6") (pin "19") (pinfunction "19_19") (pintype "passive"))
      (node (ref "JP6") (pin "20") (pinfunction "20_20") (pintype "passive"))
    )
    (net (code "92") (name "Net-(IC12C-I)") (class "Default")
      (node (ref "IC12") (pin "9") (pinfunction "I_9") (pintype "input"))
      (node (ref "JP6") (pin "27") (pinfunction "27_27") (pintype "passive"))
      (node (ref "JP6") (pin "28") (pinfunction "28_28") (pintype "passive"))
    )
    (net (code "93") (name "Net-(JP1-Pad2)") (class "Default")
      (node (ref "JP1") (pin "2") (pinfunction "2_2") (pintype "passive"))
      (node (ref "JP5") (pin "7") (pinfunction "7_7") (pintype "passive"))
      (node (ref "JP5") (pin "8") (pinfunction "8_8") (pintype "passive"))
    )
    (net (code "94") (name "Net-(JP1-Pad4)") (class "Default")
      (node (ref "JP1") (pin "4") (pinfunction "4_4") (pintype "passive"))
      (node (ref "JP5") (pin "10") (pinfunction "10_10") (pintype "passive"))
      (node (ref "JP5") (pin "9") (pinfunction "9_9") (pintype "passive"))
    )
    (net (code "95") (name "Net-(JP1-Pad6)") (class "Default")
      (node (ref "JP1") (pin "6") (pinfunction "6_6") (pintype "passive"))
      (node (ref "JP5") (pin "11") (pinfunction "11_11") (pintype "passive"))
      (node (ref "JP5") (pin "12") (pinfunction "12_12") (pintype "passive"))
    )
    (net (code "96") (name "Net-(JP3-Pad1)") (class "Default")
      (node (ref "JP3") (pin "1") (pinfunction "1_1") (pintype "passive"))
      (node (ref "JP3") (pin "2") (pinfunction "2_2") (pintype "passive"))
    )
    (net (code "97") (name "Net-(JP3-Pad3)") (class "Default")
      (node (ref "JP3") (pin "3") (pinfunction "3_3") (pintype "passive"))
      (node (ref "JP3") (pin "4") (pinfunction "4_4") (pintype "passive"))
    )
    (net (code "98") (name "Net-(JP3-Pad5)") (class "Default")
      (node (ref "JP3") (pin "5") (pinfunction "5_5") (pintype "passive"))
      (node (ref "JP3") (pin "6") (pinfunction "6_6") (pintype "passive"))
    )
    (net (code "99") (name "Net-(JP4-Pad1)") (class "Default")
      (node (ref "JP4") (pin "1") (pinfunction "1_1") (pintype "passive"))
      (node (ref "JP4") (pin "2") (pinfunction "2_2") (pintype "passive"))
    )
    (net (code "100") (name "Net-(JP4-Pad3)") (class "Default")
      (node (ref "JP4") (pin "3") (pinfunction "3_3") (pintype "passive"))
      (node (ref "JP4") (pin "4") (pinfunction "4_4") (pintype "passive"))
    )
    (net (code "101") (name "Net-(JP4-Pad5)") (class "Default")
      (node (ref "JP4") (pin "5") (pinfunction "5_5") (pintype "passive"))
      (node (ref "JP4") (pin "6") (pinfunction "6_6") (pintype "passive"))
    )
    (net (code "102") (name "Net-(JP5-Pad1)") (class "Default")
      (node (ref "JP5") (pin "1") (pinfunction "1_1") (pintype "passive"))
      (node (ref "JP5") (pin "2") (pinfunction "2_2") (pintype "passive"))
    )
    (net (code "103") (name "Net-(JP5-Pad3)") (class "Default")
      (node (ref "JP5") (pin "3") (pinfunction "3_3") (pintype "passive"))
      (node (ref "JP5") (pin "4") (pinfunction "4_4") (pintype "passive"))
    )
    (net (code "104") (name "Net-(JP5-Pad5)") (class "Default")
      (node (ref "JP5") (pin "5") (pinfunction "5_5") (pintype "passive"))
      (node (ref "JP5") (pin "6") (pinfunction "6_6") (pintype "passive"))
    )
    (net (code "105") (name "Net-(JP6-Pad1)") (class "Default")
      (node (ref "JP6") (pin "1") (pinfunction "1_1") (pintype "passive"))
      (node (ref "JP6") (pin "2") (pinfunction "2_2") (pintype "passive"))
    )
    (net (code "106") (name "Net-(JP6-Pad3)") (class "Default")
      (node (ref "JP6") (pin "3") (pinfunction "3_3") (pintype "passive"))
      (node (ref "JP6") (pin "4") (pinfunction "4_4") (pintype "passive"))
    )
    (net (code "107") (name "Net-(JP6-Pad5)") (class "Default")
      (node (ref "JP6") (pin "5") (pinfunction "5_5") (pintype "passive"))
      (node (ref "JP6") (pin "6") (pinfunction "6_6") (pintype "passive"))
    )
    (net (code "108") (name "Net-(JP6-Pad10)") (class "Default")
      (node (ref "JP6") (pin "10") (pinfunction "10_10") (pintype "passive"))
      (node (ref "JP6") (pin "9") (pinfunction "9_9") (pintype "passive"))
    )
    (net (code "109") (name "Net-(JP6-Pad13)") (class "Default")
      (node (ref "JP6") (pin "13") (pinfunction "13_13") (pintype "passive"))
      (node (ref "JP6") (pin "14") (pinfunction "14_14") (pintype "passive"))
    )
    (net (code "110") (name "Net-(JP6-Pad17)") (class "Default")
      (node (ref "JP6") (pin "17") (pinfunction "17_17") (pintype "passive"))
      (node (ref "JP6") (pin "18") (pinfunction "18_18") (pintype "passive"))
    )
    (net (code "111") (name "Net-(JP6-Pad21)") (class "Default")
      (node (ref "JP6") (pin "21") (pinfunction "21_21") (pintype "passive"))
      (node (ref "JP6") (pin "22") (pinfunction "22_22") (pintype "passive"))
    )
    (net (code "112") (name "Net-(JP6-Pad25)") (class "Default")
      (node (ref "JP6") (pin "25") (pinfunction "25_25") (pintype "passive"))
      (node (ref "JP6") (pin "26") (pinfunction "26_26") (pintype "passive"))
    )
    (net (code "113") (name "Net-(JP6-Pad29)") (class "Default")
      (node (ref "JP6") (pin "29") (pinfunction "29_29") (pintype "passive"))
      (node (ref "JP6") (pin "30") (pinfunction "30_30") (pintype "passive"))
    )
    (net (code "114") (name "Net-(JP6-Pad31)") (class "Default")
      (node (ref "JP6") (pin "31") (pinfunction "31_31") (pintype "passive"))
      (node (ref "JP6") (pin "32") (pinfunction "32_32") (pintype "passive"))
    )
    (net (code "115") (name "Net-(JP6-Pad33)") (class "Default")
      (node (ref "JP6") (pin "33") (pinfunction "33_33") (pintype "passive"))
      (node (ref "JP6") (pin "34") (pinfunction "34_34") (pintype "passive"))
    )
    (net (code "116") (name "Net-(JP6-Pad35)") (class "Default")
      (node (ref "JP6") (pin "35") (pinfunction "35_35") (pintype "passive"))
      (node (ref "JP6") (pin "36") (pinfunction "36_36") (pintype "passive"))
    )
    (net (code "117") (name "unconnected-(G2-+-Pad+@1)") (class "Default")
      (node (ref "G2") (pin "+@1") (pinfunction "+_+@1") (pintype "passive"))
    )
    (net (code "118") (name "unconnected-(IC3A-Y6-Pad13)") (class "Default")
      (node (ref "IC3") (pin "13") (pinfunction "Y6_13") (pintype "tri_state"))
    )
    (net (code "119") (name "unconnected-(IC3A-Y7-Pad12)") (class "Default")
      (node (ref "IC3") (pin "12") (pinfunction "Y7_12") (pintype "tri_state"))
    )
    (net (code "120") (name "unconnected-(IC3A-Y8-Pad11)") (class "Default")
      (node (ref "IC3") (pin "11") (pinfunction "Y8_11") (pintype "tri_state"))
    )
    (net (code "121") (name "unconnected-(IC6A-Y6-Pad13)") (class "Default")
      (node (ref "IC6") (pin "13") (pinfunction "Y6_13") (pintype "tri_state"))
    )
    (net (code "122") (name "unconnected-(IC6A-Y7-Pad12)") (class "Default")
      (node (ref "IC6") (pin "12") (pinfunction "Y7_12") (pintype "tri_state"))
    )
    (net (code "123") (name "unconnected-(IC6A-Y8-Pad11)") (class "Default")
      (node (ref "IC6") (pin "11") (pinfunction "Y8_11") (pintype "tri_state"))
    )
    (net (code "124") (name "unconnected-(IC8A-Y8-Pad11)") (class "Default")
      (node (ref "IC8") (pin "11") (pinfunction "Y8_11") (pintype "tri_state"))
    )
    (net (code "125") (name "unconnected-(IC12E-O-Pad4)") (class "Default")
      (node (ref "IC12") (pin "4") (pinfunction "O_4") (pintype "output"))
    )
    (net (code "126") (name "unconnected-(IC12F-O-Pad6)") (class "Default")
      (node (ref "IC12") (pin "6") (pinfunction "O_6") (pintype "output"))
    )
    (net (code "127") (name "unconnected-(JP3-Pad33)") (class "Default")
      (node (ref "JP3") (pin "33") (pinfunction "33_33") (pintype "passive"))
    )
    (net (code "128") (name "unconnected-(JP3-Pad34)") (class "Default")
      (node (ref "JP3") (pin "34") (pinfunction "34_34") (pintype "passive"))
    )
    (net (code "129") (name "unconnected-(JP3-Pad35)") (class "Default")
      (node (ref "JP3") (pin "35") (pinfunction "35_35") (pintype "passive"))
    )
    (net (code "130") (name "unconnected-(JP3-Pad36)") (class "Default")
      (node (ref "JP3") (pin "36") (pinfunction "36_36") (pintype "passive"))
    )
    (net (code "131") (name "unconnected-(JP4-Pad33)") (class "Default")
      (node (ref "JP4") (pin "33") (pinfunction "33_33") (pintype "passive"))
    )
    (net (code "132") (name "unconnected-(JP4-Pad34)") (class "Default")
      (node (ref "JP4") (pin "34") (pinfunction "34_34") (pintype "passive"))
    )
    (net (code "133") (name "unconnected-(JP4-Pad35)") (class "Default")
      (node (ref "JP4") (pin "35") (pinfunction "35_35") (pintype "passive"))
    )
    (net (code "134") (name "unconnected-(JP4-Pad36)") (class "Default")
      (node (ref "JP4") (pin "36") (pinfunction "36_36") (pintype "passive"))
    )
  )
)
